# UCC.net
KiCad netlist of a schematic drawn in EasyEDA Pro
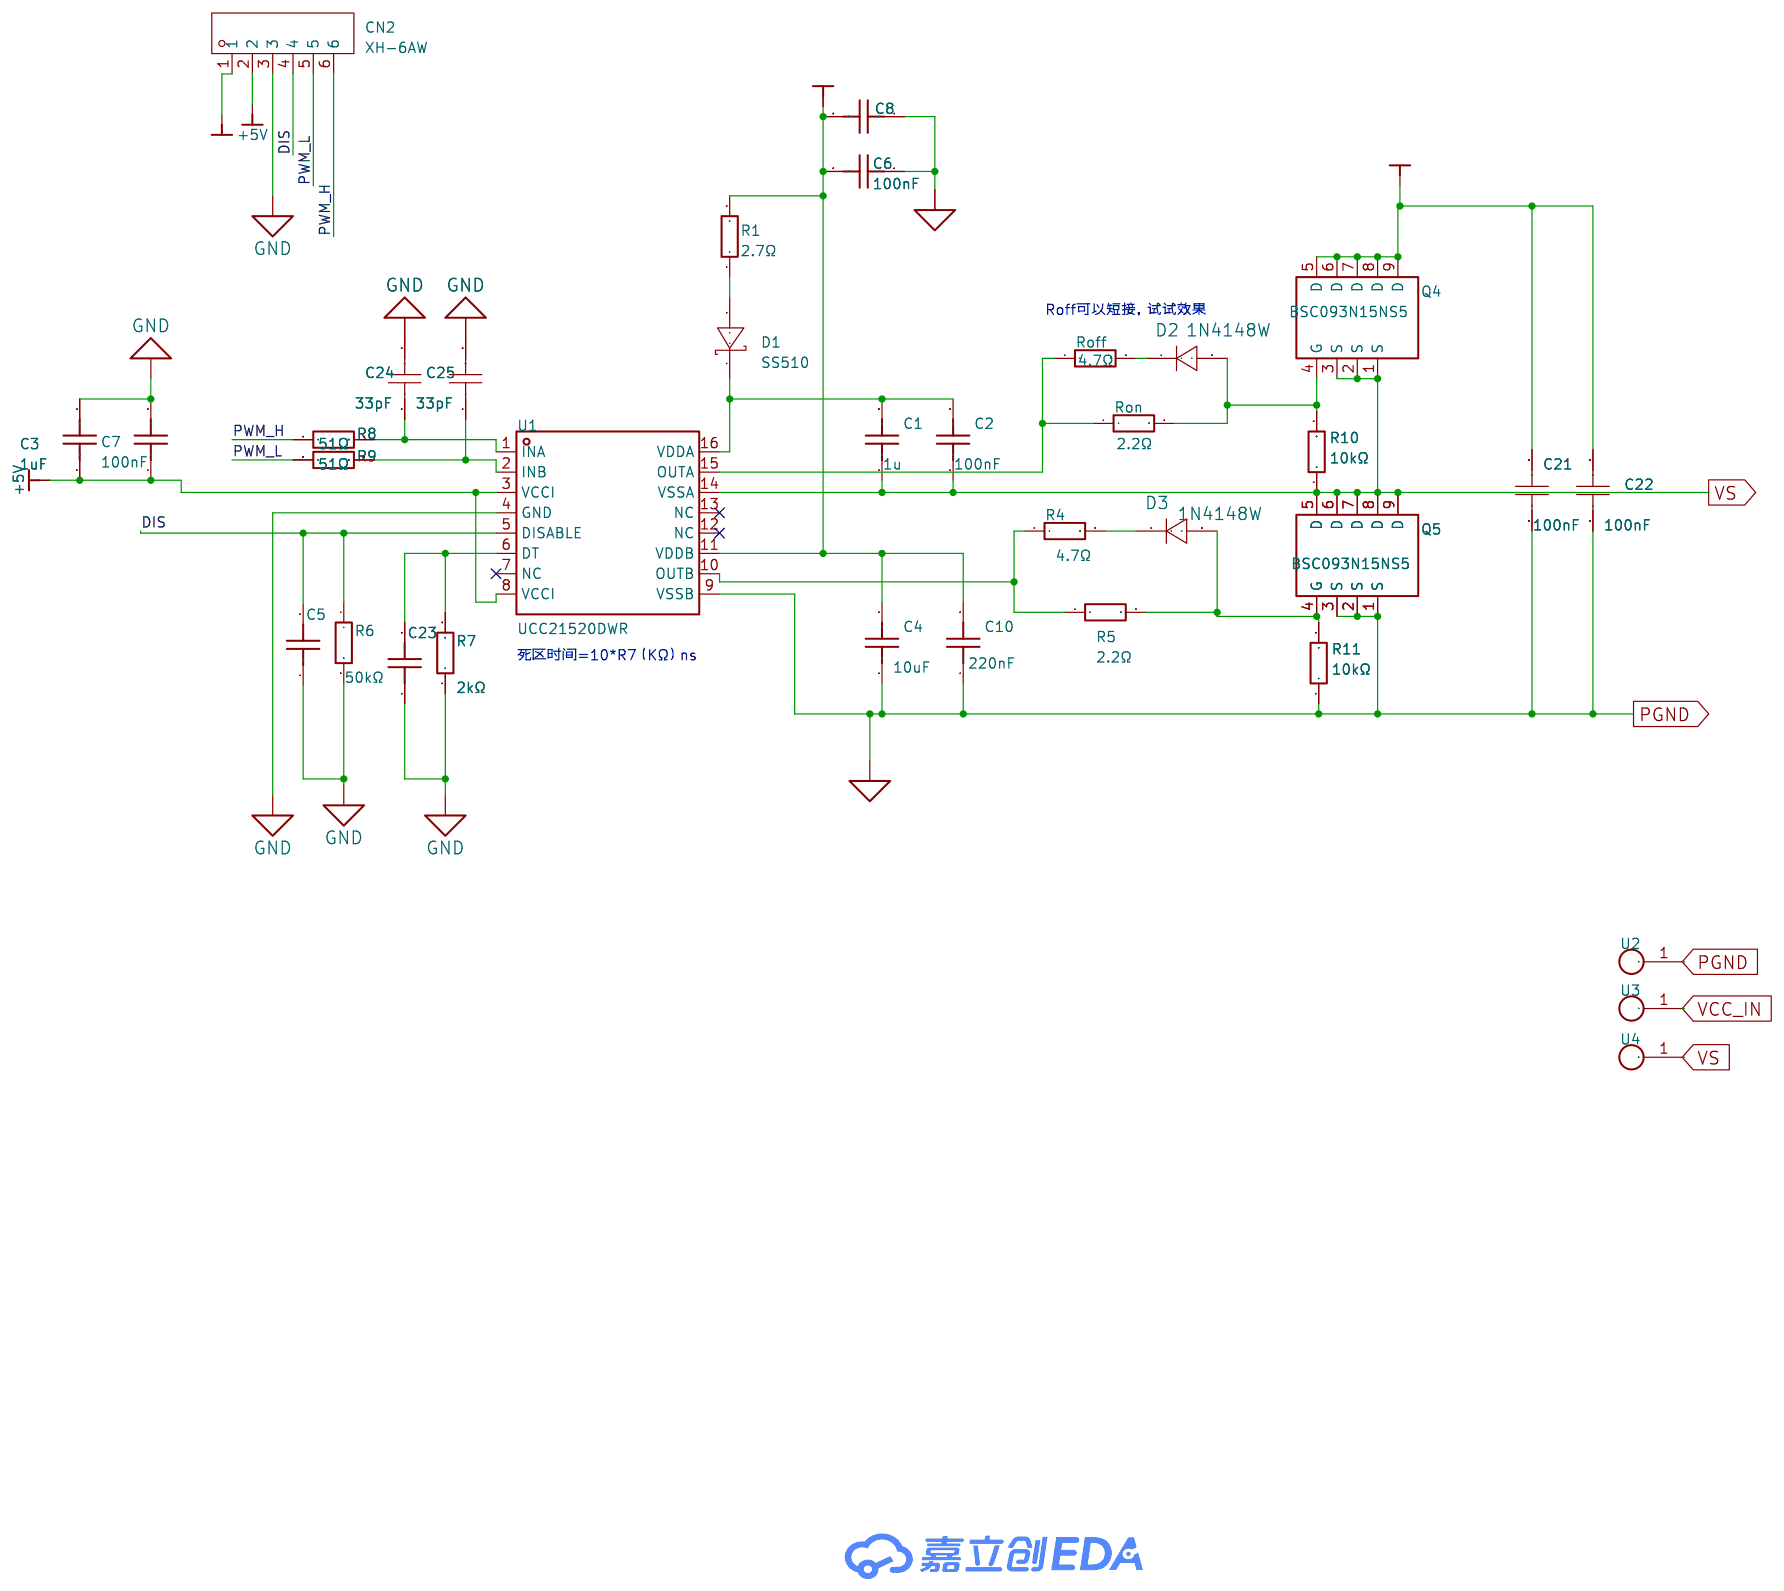
[diagram p0: schematic sheet]

(export (version "E")
  (design (tool "Eeschema 10.0.6"))
  (components
    (comp (ref "C1")
      (value "1u")
      (footprint "easyedapro:C0805")
      (libsource (lib "easyedapro") (part "Capacitance"))
    )
    (comp (ref "C2")
      (value "100nF")
      (footprint "easyedapro:C0805")
      (libsource (lib "easyedapro") (part "Capacitance"))
    )
    (comp (ref "C3")
      (value "1uF")
      (fields
        (field (name "Manufacturer Part") "CC0603KRX7R9BB104")
        (field (name "Manufacturer") "YAGEO(国巨)")
      )
      (libsource (lib "easyedapro") (part "CapAcitance"))
    )
    (comp (ref "C4")
      (value "10uF")
      (fields
        (field (name "Manufacturer Part") "CL10A105KB8NNNC")
        (field (name "Manufacturer") "SAMSUNG(三星)")
      )
      (libsource (lib "easyedapro") (part "CapAcitance"))
    )
    (comp (ref "C5")
      (value "1nF")
      (fields
        (field (name "Manufacturer Part") "CL10B102KB8NNNC")
        (field (name "Manufacturer") "SAMSUNG(三星)")
      )
      (libsource (lib "easyedapro") (part "CapAcitance"))
    )
    (comp (ref "C6")
      (value "100nF")
      (description "容值:1uF;精度:±10%;额定电压:50V;温度系数:X5R;")
      (libsource (lib "easyedapro") (part "CapAcitance"))
    )
    (comp (ref "C7")
      (value "100nF")
      (fields
        (field (name "Manufacturer Part") "CL10A105KB8NNNC")
        (field (name "Manufacturer") "SAMSUNG(三星)")
      )
      (libsource (lib "easyedapro") (part "CapAcitance"))
    )
    (comp (ref "C8")
      (value "10uF")
      (description "容值:10uF;精度:±10%;额定电压:10V;温度系数:X5R;")
      (libsource (lib "easyedapro") (part "CapAcitance"))
    )
    (comp (ref "C10")
      (value "220nF")
      (fields
        (field (name "Manufacturer Part") "CC0603KRX7R9BB104")
        (field (name "Manufacturer") "YAGEO(国巨)")
      )
      (libsource (lib "easyedapro") (part "CapAcitance"))
    )
    (comp (ref "C21")
      (value "100nF")
      (footprint "easyedapro:C1206")
      (description "容值:4.7uF;精度:±10%;额定电压:50V;温度系数:X7R;")
      (fields (field (name "Manufacturer Part") "AM06B475K500NT") (field (name "Manufacturer") "FH(风华)"))
      (libsource (lib "easyedapro") (part "AM06B475K500NT"))
    )
    (comp (ref "C22")
      (value "100nF")
      (footprint "easyedapro:C1206")
      (description "容值:4.7uF;精度:±10%;额定电压:50V;温度系数:X7R;")
      (fields (field (name "Manufacturer Part") "AM06B475K500NT") (field (name "Manufacturer") "FH(风华)"))
      (libsource (lib "easyedapro") (part "AM06B475K500NT"))
    )
    (comp (ref "C23")
      (value "1nF")
      (fields
        (field (name "Manufacturer Part") "CL10B102KB8NNNC")
        (field (name "Manufacturer") "SAMSUNG(三星)")
      )
      (libsource (lib "easyedapro") (part "CapAcitance"))
    )
    (comp (ref "C24")
      (value "33pF")
      (fields
        (field (name "Manufacturer Part") "CC0603JRNPO9BN330")
        (field (name "Manufacturer") "YAGEO(国巨)")
      )
      (libsource (lib "easyedapro") (part "CapAcitance"))
    )
    (comp (ref "C25")
      (value "33pF")
      (fields
        (field (name "Manufacturer Part") "CC0603JRNPO9BN330")
        (field (name "Manufacturer") "YAGEO(国巨)")
      )
      (libsource (lib "easyedapro") (part "CapAcitance"))
    )
    (comp (ref "CN2")
      (value "XH-6AW")
      (footprint "easyedapro:CONN-TH_6P-P2.54_HCTL_XH-6AW_C2908615")
      (fields (field (name "Manufacturer") "HCTL(华灿天禄)"))
      (libsource (lib "easyedapro") (part "XH-6AW_C2908615"))
    )
    (comp (ref "D1")
      (value "SS510")
      (footprint "easyedapro:SMA_L4.3-W2.6-LS5.2-RD")
      (description "100V,5A,VF=0.85V@5A")
      (fields (field (name "Manufacturer") "MDD"))
      (libsource (lib "easyedapro") (part "SS510_C65010"))
    )
    (comp (ref "D2")
      (value "1N4148W")
      (fields (field (name "Manufacturer") "CJ(江苏长电/长晶)"))
      (libsource (lib "easyedapro") (part "1N4148W"))
    )
    (comp (ref "D3")
      (value "1N4148W")
      (fields (field (name "Manufacturer") "CJ(江苏长电/长晶)"))
      (libsource (lib "easyedapro") (part "1N4148W"))
    )
    (comp (ref "Q4")
      (value "BSC093N15NS5")
      (footprint "easyedapro:PG-TDSON-8_L5.0-W6.0-P1.27-LS6.2-BL-EP")
      (fields (field (name "Manufacturer") "Infineon(英飞凌)"))
      (libsource (lib "easyedapro") (part "BSC093N15NS5"))
    )
    (comp (ref "Q5")
      (value "BSC093N15NS5")
      (footprint "easyedapro:PG-TDSON-8_L5.0-W6.0-P1.27-LS6.2-BL-EP")
      (fields (field (name "Manufacturer") "Infineon(英飞凌)"))
      (libsource (lib "easyedapro") (part "BSC093N15NS5"))
    )
    (comp (ref "R1")
      (value "2.7Ω")
      (footprint "easyedapro:R1206")
      (fields (field (name "Manufacturer Part") "RC0805FR-072R2L") (field (name "Manufacturer") "YAGEO(国巨)"))
      (libsource (lib "easyedapro") (part "电阻_1"))
    )
    (comp (ref "R4")
      (value "4.7Ω")
      (footprint "easyedapro:R1206")
      (libsource (lib "easyedapro") (part "电阻_1"))
    )
    (comp (ref "R5")
      (value "2.2Ω")
      (footprint "easyedapro:R1206")
      (libsource (lib "easyedapro") (part "电阻_1"))
    )
    (comp (ref "R6")
      (value "50kΩ")
      (footprint "easyedapro:R1206")
      (fields (field (name "Manufacturer Part") "RC0603FR-0710KL") (field (name "Manufacturer") "YAGEO(国巨)"))
      (libsource (lib "easyedapro") (part "电阻_1"))
    )
    (comp (ref "R7")
      (value "2kΩ")
      (footprint "easyedapro:R1206")
      (fields (field (name "Manufacturer Part") "RC0603FR-0710KL") (field (name "Manufacturer") "YAGEO(国巨)"))
      (libsource (lib "easyedapro") (part "电阻_1"))
    )
    (comp (ref "R8")
      (value "51Ω")
      (footprint "easyedapro:R1206")
      (fields
        (field (name "Manufacturer Part") "0603WAF510JT5E")
        (field (name "Manufacturer") "UNI-ROYAL(厚声)")
      )
      (libsource (lib "easyedapro") (part "电阻_1"))
    )
    (comp (ref "R9")
      (value "51Ω")
      (footprint "easyedapro:R1206")
      (fields
        (field (name "Manufacturer Part") "0603WAF510JT5E")
        (field (name "Manufacturer") "UNI-ROYAL(厚声)")
      )
      (libsource (lib "easyedapro") (part "电阻_1"))
    )
    (comp (ref "R10")
      (value "10kΩ")
      (footprint "easyedapro:R1206")
      (fields
        (field (name "Manufacturer Part") "0603WAF1002T5E")
        (field (name "Manufacturer") "UNI-ROYAL(厚声)")
      )
      (libsource (lib "easyedapro") (part "电阻_1"))
    )
    (comp (ref "R11")
      (value "10kΩ")
      (footprint "easyedapro:R1206")
      (fields
        (field (name "Manufacturer Part") "0603WAF1002T5E")
        (field (name "Manufacturer") "UNI-ROYAL(厚声)")
      )
      (libsource (lib "easyedapro") (part "电阻_1"))
    )
    (comp (ref "Roff")
      (value "4.7Ω")
      (footprint "easyedapro:R1206")
      (libsource (lib "easyedapro") (part "电阻_1"))
    )
    (comp (ref "Ron")
      (value "2.2Ω")
      (footprint "easyedapro:R1206")
      (libsource (lib "easyedapro") (part "电阻_1"))
    )
    (comp (ref "U1")
      (value "UCC21520DWR")
      (footprint "easyedapro:SOIC-16_L10.3-W7.5-P1.27-LS10.3-BL")
      (fields (field (name "Manufacturer") "TI(德州仪器)"))
      (libsource (lib "easyedapro") (part "UCC21520DWR"))
    )
    (comp (ref "U2")
      (value "~")
      (footprint "easyedapro:3.5mm香蕉头")
      (libsource (lib "easyedapro") (part "3.5mm香蕉头"))
    )
    (comp (ref "U3")
      (value "~")
      (footprint "easyedapro:3.5mm香蕉头")
      (libsource (lib "easyedapro") (part "3.5mm香蕉头"))
    )
    (comp (ref "U4")
      (value "~")
      (footprint "easyedapro:3.5mm香蕉头")
      (libsource (lib "easyedapro") (part "3.5mm香蕉头"))
    )
  )
  (nets
    (net (code "1") (name "+5V") (class "Default")
      (node (ref "C3") (pin "1") (pinfunction "1_1") (pintype "input"))
      (node (ref "C7") (pin "1") (pinfunction "1_1") (pintype "input"))
      (node (ref "CN2") (pin "2") (pinfunction "2_2") (pintype "unspecified"))
      (node (ref "U1") (pin "3") (pinfunction "VCCI_3") (pintype "input"))
      (node (ref "U1") (pin "8") (pinfunction "VCCI_8") (pintype "input"))
    )
    (net (code "2") (name "+12V") (class "Default")
      (node (ref "C10") (pin "2") (pinfunction "2_2") (pintype "input"))
      (node (ref "C4") (pin "2") (pinfunction "2_2") (pintype "input"))
      (node (ref "C6") (pin "2") (pinfunction "2_2") (pintype "input"))
      (node (ref "C8") (pin "2") (pinfunction "2_2") (pintype "input"))
      (node (ref "CN2") (pin "1") (pinfunction "1_1") (pintype "unspecified"))
      (node (ref "R1") (pin "2") (pinfunction "2_2") (pintype "input"))
      (node (ref "U1") (pin "11") (pinfunction "VDDB_11") (pintype "input"))
    )
    (net (code "3") (name "/DIS") (class "Default")
      (node (ref "C5") (pin "2") (pinfunction "2_2") (pintype "input"))
      (node (ref "CN2") (pin "4") (pinfunction "4_4") (pintype "unspecified"))
      (node (ref "R6") (pin "1") (pinfunction "1_1") (pintype "input"))
      (node (ref "U1") (pin "5") (pinfunction "DISABLE_5") (pintype "input"))
    )
    (net (code "4") (name "/PWM_H") (class "Default")
      (node (ref "CN2") (pin "6") (pinfunction "6_6") (pintype "unspecified"))
      (node (ref "R8") (pin "1") (pinfunction "1_1") (pintype "input"))
    )
    (net (code "5") (name "/PWM_L") (class "Default")
      (node (ref "CN2") (pin "5") (pinfunction "5_5") (pintype "unspecified"))
      (node (ref "R9") (pin "1") (pinfunction "1_1") (pintype "input"))
    )
    (net (code "6") (name "GND") (class "Default")
      (node (ref "C23") (pin "1") (pinfunction "1_1") (pintype "input"))
      (node (ref "C24") (pin "2") (pinfunction "2_2") (pintype "input"))
      (node (ref "C25") (pin "2") (pinfunction "2_2") (pintype "input"))
      (node (ref "C3") (pin "2") (pinfunction "2_2") (pintype "input"))
      (node (ref "C5") (pin "1") (pinfunction "1_1") (pintype "input"))
      (node (ref "C7") (pin "2") (pinfunction "2_2") (pintype "input"))
      (node (ref "CN2") (pin "3") (pinfunction "3_3") (pintype "unspecified"))
      (node (ref "R6") (pin "2") (pinfunction "2_2") (pintype "input"))
      (node (ref "R7") (pin "1") (pinfunction "1_1") (pintype "input"))
      (node (ref "U1") (pin "4") (pinfunction "GND_4") (pintype "input"))
    )
    (net (code "7") (name "Net-(D1-A)") (class "Default")
      (node (ref "D1") (pin "2") (pinfunction "A_2") (pintype "input"))
      (node (ref "R1") (pin "1") (pinfunction "1_1") (pintype "input"))
    )
    (net (code "8") (name "Net-(D1-K)") (class "Default")
      (node (ref "C1") (pin "2") (pinfunction "2_2") (pintype "input"))
      (node (ref "C2") (pin "2") (pinfunction "2_2") (pintype "input"))
      (node (ref "D1") (pin "1") (pinfunction "K_1") (pintype "input"))
      (node (ref "U1") (pin "16") (pinfunction "VDDA_16") (pintype "input"))
    )
    (net (code "9") (name "Net-(D2-A)") (class "Default")
      (node (ref "D2") (pin "2") (pinfunction "A_2") (pintype "input"))
      (node (ref "Q4") (pin "4") (pinfunction "G_4") (pintype "unspecified"))
      (node (ref "R10") (pin "2") (pinfunction "2_2") (pintype "input"))
      (node (ref "Ron") (pin "2") (pinfunction "2_2") (pintype "input"))
    )
    (net (code "10") (name "Net-(D2-K)") (class "Default")
      (node (ref "D2") (pin "1") (pinfunction "K_1") (pintype "input"))
      (node (ref "Roff") (pin "2") (pinfunction "2_2") (pintype "input"))
    )
    (net (code "11") (name "Net-(D3-A)") (class "Default")
      (node (ref "D3") (pin "2") (pinfunction "A_2") (pintype "input"))
      (node (ref "Q5") (pin "4") (pinfunction "G_4") (pintype "unspecified"))
      (node (ref "R11") (pin "2") (pinfunction "2_2") (pintype "input"))
      (node (ref "R5") (pin "2") (pinfunction "2_2") (pintype "input"))
    )
    (net (code "12") (name "Net-(D3-K)") (class "Default")
      (node (ref "D3") (pin "1") (pinfunction "K_1") (pintype "input"))
      (node (ref "R4") (pin "2") (pinfunction "2_2") (pintype "input"))
    )
    (net (code "13") (name "Net-(U1-DT)") (class "Default")
      (node (ref "C23") (pin "2") (pinfunction "2_2") (pintype "input"))
      (node (ref "R7") (pin "2") (pinfunction "2_2") (pintype "input"))
      (node (ref "U1") (pin "6") (pinfunction "DT_6") (pintype "input"))
    )
    (net (code "14") (name "Net-(U1-INA)") (class "Default")
      (node (ref "C24") (pin "1") (pinfunction "1_1") (pintype "input"))
      (node (ref "R8") (pin "2") (pinfunction "2_2") (pintype "input"))
      (node (ref "U1") (pin "1") (pinfunction "INA_1") (pintype "input"))
    )
    (net (code "15") (name "Net-(U1-INB)") (class "Default")
      (node (ref "C25") (pin "1") (pinfunction "1_1") (pintype "input"))
      (node (ref "R9") (pin "2") (pinfunction "2_2") (pintype "input"))
      (node (ref "U1") (pin "2") (pinfunction "INB_2") (pintype "input"))
    )
    (net (code "16") (name "Net-(U1-OUTA)") (class "Default")
      (node (ref "Roff") (pin "1") (pinfunction "1_1") (pintype "input"))
      (node (ref "Ron") (pin "1") (pinfunction "1_1") (pintype "input"))
      (node (ref "U1") (pin "15") (pinfunction "OUTA_15") (pintype "input"))
    )
    (net (code "17") (name "Net-(U1-OUTB)") (class "Default")
      (node (ref "R4") (pin "1") (pinfunction "1_1") (pintype "input"))
      (node (ref "R5") (pin "1") (pinfunction "1_1") (pintype "input"))
      (node (ref "U1") (pin "10") (pinfunction "OUTB_10") (pintype "input"))
    )
    (net (code "18") (name "PGND") (class "Default")
      (node (ref "C10") (pin "1") (pinfunction "1_1") (pintype "input"))
      (node (ref "C21") (pin "1") (pinfunction "1_1") (pintype "unspecified"))
      (node (ref "C22") (pin "1") (pinfunction "1_1") (pintype "unspecified"))
      (node (ref "C4") (pin "1") (pinfunction "1_1") (pintype "input"))
      (node (ref "C6") (pin "1") (pinfunction "1_1") (pintype "input"))
      (node (ref "C8") (pin "1") (pinfunction "1_1") (pintype "input"))
      (node (ref "Q5") (pin "1") (pinfunction "S_1") (pintype "unspecified"))
      (node (ref "Q5") (pin "2") (pinfunction "S_2") (pintype "unspecified"))
      (node (ref "Q5") (pin "3") (pinfunction "S_3") (pintype "unspecified"))
      (node (ref "R11") (pin "1") (pinfunction "1_1") (pintype "input"))
      (node (ref "U1") (pin "9") (pinfunction "VSSB_9") (pintype "input"))
      (node (ref "U2") (pin "1") (pinfunction "1_1") (pintype "input"))
    )
    (net (code "19") (name "VCC_IN") (class "Default")
      (node (ref "C21") (pin "2") (pinfunction "2_2") (pintype "unspecified"))
      (node (ref "C22") (pin "2") (pinfunction "2_2") (pintype "unspecified"))
      (node (ref "Q4") (pin "5") (pinfunction "D_5") (pintype "unspecified"))
      (node (ref "Q4") (pin "6") (pinfunction "D_6") (pintype "unspecified"))
      (node (ref "Q4") (pin "7") (pinfunction "D_7") (pintype "unspecified"))
      (node (ref "Q4") (pin "8") (pinfunction "D_8") (pintype "unspecified"))
      (node (ref "Q4") (pin "9") (pinfunction "D_9") (pintype "unspecified"))
      (node (ref "U3") (pin "1") (pinfunction "1_1") (pintype "input"))
    )
    (net (code "20") (name "VS") (class "Default")
      (node (ref "C1") (pin "1") (pinfunction "1_1") (pintype "input"))
      (node (ref "C2") (pin "1") (pinfunction "1_1") (pintype "input"))
      (node (ref "Q4") (pin "1") (pinfunction "S_1") (pintype "unspecified"))
      (node (ref "Q4") (pin "2") (pinfunction "S_2") (pintype "unspecified"))
      (node (ref "Q4") (pin "3") (pinfunction "S_3") (pintype "unspecified"))
      (node (ref "Q5") (pin "5") (pinfunction "D_5") (pintype "unspecified"))
      (node (ref "Q5") (pin "6") (pinfunction "D_6") (pintype "unspecified"))
      (node (ref "Q5") (pin "7") (pinfunction "D_7") (pintype "unspecified"))
      (node (ref "Q5") (pin "8") (pinfunction "D_8") (pintype "unspecified"))
      (node (ref "Q5") (pin "9") (pinfunction "D_9") (pintype "unspecified"))
      (node (ref "R10") (pin "1") (pinfunction "1_1") (pintype "input"))
      (node (ref "U1") (pin "14") (pinfunction "VSSA_14") (pintype "input"))
      (node (ref "U4") (pin "1") (pinfunction "1_1") (pintype "input"))
    )
    (net (code "21") (name "unconnected-(U1-NC-Pad7)") (class "Default")
      (node (ref "U1") (pin "7") (pinfunction "NC_7") (pintype "input+no_connect"))
    )
    (net (code "22") (name "unconnected-(U1-NC-Pad12)") (class "Default")
      (node (ref "U1") (pin "12") (pinfunction "NC_12") (pintype "input+no_connect"))
    )
    (net (code "23") (name "unconnected-(U1-NC-Pad13)") (class "Default")
      (node (ref "U1") (pin "13") (pinfunction "NC_13") (pintype "input+no_connect"))
    )
  )
)
